# sem4200.net
KiCad netlist of a schematic drawn in Altium Designer
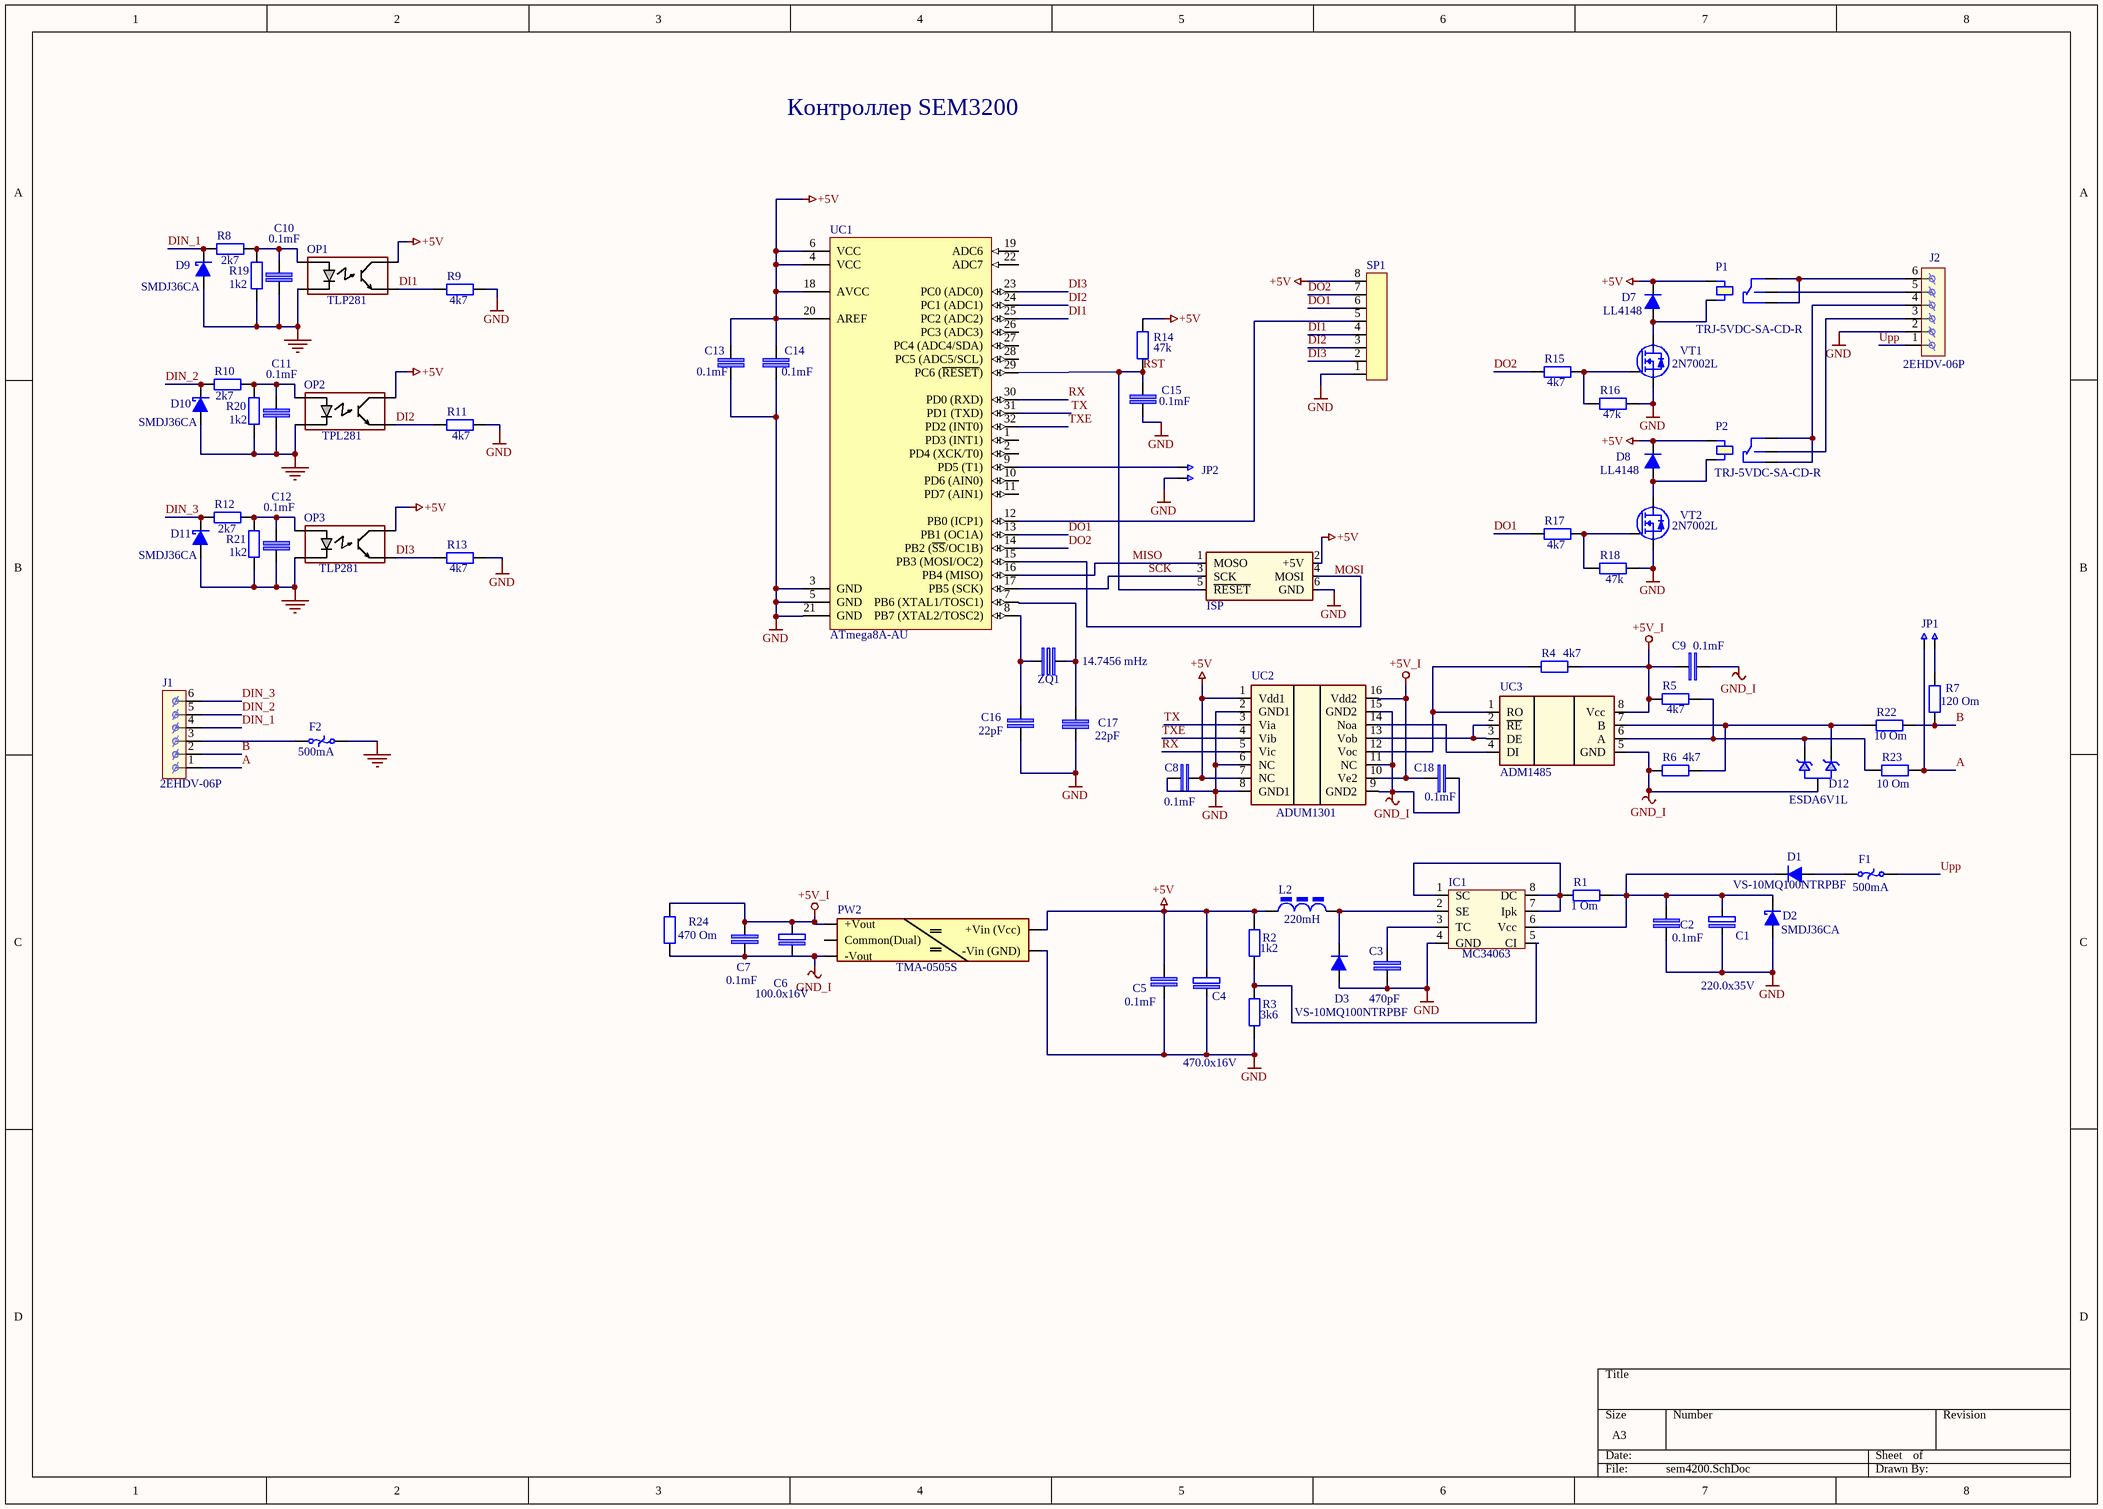
[diagram p0: sem4200.SchDoc]

(export (version "E")
  (design (tool "Eeschema 10.0.6"))
  (components
    (comp (ref "C1")
      (value "220.0x35V")
      (footprint "Cap_2(10x12.5)")
      (libsource (lib "Lib_my1") (part "Cap_pol2"))
    )
    (comp (ref "C2")
      (value "0.1mF")
      (footprint "CAPC2113X13N_0805")
      (fields (field (name "Comment") "0.1"))
      (libsource (lib "") (part "cap_1_1"))
    )
    (comp (ref "C3")
      (value "470pF")
      (footprint "CAPC2113X13N_0805")
      (fields (field (name "Comment") "470 pF"))
      (libsource (lib "") (part "cap_1_1"))
    )
    (comp (ref "C4")
      (value "470.0x16V")
      (footprint "Cap_2(10x12.5)")
      (fields (field (name "Comment") "470.0x35V"))
      (libsource (lib "Lib_my1") (part "Cap_pol2"))
    )
    (comp (ref "C5")
      (value "0.1mF")
      (footprint "CAPC2113X13N_0805")
      (fields (field (name "Comment") "0.1"))
      (libsource (lib "") (part "cap_1_1"))
    )
    (comp (ref "C6")
      (value "100.0x16V")
      (footprint "Cap_4(5x10)")
      (fields (field (name "Comment") "22.0x16V"))
      (libsource (lib "") (part "Cap_pol2_1"))
    )
    (comp (ref "C7")
      (value "0.1mF")
      (footprint "CAPC2113X13N_0805")
      (fields (field (name "Comment") "0.1"))
      (libsource (lib "Lib_my1") (part "cap_1"))
    )
    (comp (ref "C8")
      (value "0.1mF")
      (footprint "CAPC2113X13N_0805")
      (fields (field (name "Comment") "0.1"))
      (libsource (lib "Lib_my1") (part "cap_1"))
    )
    (comp (ref "C9")
      (value "0.1mF")
      (footprint "CAPC2113X13N_0805")
      (fields (field (name "Comment") "0.1"))
      (libsource (lib "Lib_my1") (part "cap_1"))
    )
    (comp (ref "C10")
      (value "0.1mF")
      (footprint "CAPC2113X13N_0805")
      (fields (field (name "Comment") "0.1"))
      (libsource (lib "Lib_my1") (part "cap_1"))
    )
    (comp (ref "C11")
      (value "0.1mF")
      (footprint "CAPC2113X13N_0805")
      (fields (field (name "Comment") "0.1"))
      (libsource (lib "Lib_my1") (part "cap_1"))
    )
    (comp (ref "C12")
      (value "0.1mF")
      (footprint "CAPC2113X13N_0805")
      (fields (field (name "Comment") "0.1"))
      (libsource (lib "Lib_my1") (part "cap_1"))
    )
    (comp (ref "C13")
      (value "0.1mF")
      (footprint "CAPC2113X13N_0805")
      (fields (field (name "Comment") "0.1"))
      (libsource (lib "Lib_my1") (part "cap_1"))
    )
    (comp (ref "C14")
      (value "0.1mF")
      (footprint "CAPC2113X13N_0805")
      (fields (field (name "Comment") "0.1"))
      (libsource (lib "Lib_my1") (part "cap_1"))
    )
    (comp (ref "C15")
      (value "0.1mF")
      (footprint "CAPC2113X13N_0805")
      (fields (field (name "Comment") "0.1"))
      (libsource (lib "") (part "cap_1_1"))
    )
    (comp (ref "C16")
      (value "22pF")
      (footprint "CAPC2113X13N_0805")
      (fields (field (name "Comment") "20p"))
      (libsource (lib "") (part "cap_1_1"))
    )
    (comp (ref "C17")
      (value "22pF")
      (footprint "CAPC2113X13N_0805")
      (fields (field (name "Comment") "20p"))
      (libsource (lib "") (part "cap_1_1"))
    )
    (comp (ref "C18")
      (value "0.1mF")
      (footprint "CAPC2113X13N_0805")
      (fields (field (name "Comment") "0.1"))
      (libsource (lib "") (part "cap_1_2"))
    )
    (comp (ref "D1")
      (value "SS18")
      (footprint "DIOD_SMA")
      (fields (field (name "TYPE") "VS-10MQ100NTRPBF"))
      (libsource (lib "Lib_my1") (part "Diod_30BQ100"))
    )
    (comp (ref "D2")
      (value "SMDJ36CA")
      (footprint "SMB_1")
      (fields (field (name "TYPE") "SMDJ36CA"))
      (libsource (lib "Lib_my1") (part "Diodes_SMB"))
    )
    (comp (ref "D3")
      (value "SS18")
      (footprint "DIOD_SMA")
      (fields (field (name "TYPE") "VS-10MQ100NTRPBF"))
      (libsource (lib "Lib_my1") (part "Diod_30BQ100"))
    )
    (comp (ref "D7")
      (value "LL4148")
      (footprint "DIOD_MELF_SOD80")
      (fields (field (name "TYPE") "LL4148"))
      (libsource (lib "Lib_my1") (part "Diodes_4148"))
    )
    (comp (ref "D8")
      (value "LL4148")
      (footprint "DIOD_MELF_SOD80")
      (fields (field (name "TYPE") "LL4148"))
      (libsource (lib "Lib_my1") (part "Diodes_4148"))
    )
    (comp (ref "D9")
      (value "SMDJ36CA")
      (footprint "SMB_1")
      (fields (field (name "TYPE") "SMDJ36CA"))
      (libsource (lib "Lib_my1") (part "Diodes_SMB"))
    )
    (comp (ref "D10")
      (value "SMDJ36CA")
      (footprint "SMB_1")
      (fields (field (name "TYPE") "SMDJ36CA"))
      (libsource (lib "Lib_my1") (part "Diodes_SMB"))
    )
    (comp (ref "D11")
      (value "SMDJ36CA")
      (footprint "SMB_1")
      (fields (field (name "TYPE") "SMDJ36CA"))
      (libsource (lib "Lib_my1") (part "Diodes_SMB"))
    )
    (comp (ref "D12")
      (value "ESDA6V1L")
      (footprint "SOT23_diod_ESDA")
      (fields (field (name "TYPE") "ESDA6V1L"))
      (libsource (lib "Lib_my1") (part "Diod_ESDA"))
    )
    (comp (ref "F1") (value "500mA") (footprint "Fuse_termo") (libsource (lib "Lib_my1") (part "Fuse_term")))
    (comp (ref "F2") (value "500mA") (footprint "Fuse_termo") (libsource (lib "Lib_my1") (part "Fuse_term")))
    (comp (ref "IC1")
      (value "MC34063")
      (footprint "SOIC_SO-8")
      (fields (field (name "TYPE") "MC34063"))
      (libsource (lib "Lib_my1") (part "MC34063_1"))
    )
    (comp (ref "ISP") (value "ISP") (footprint "ISP_1") (libsource (lib "Lib_my1") (part "ISP_1")))
    (comp (ref "J1")
      (value "Conn_6x1")
      (footprint "conn6X1")
      (fields (field (name "TYPE") "2EHDV-06P"))
      (libsource (lib "") (part "Conn_6x1_1"))
    )
    (comp (ref "J2")
      (value "Conn_6x1")
      (footprint "conn6X1")
      (fields (field (name "TYPE") "2EHDV-06P"))
      (libsource (lib "Lib_my1") (part "Conn_6x1"))
    )
    (comp (ref "JP1") (value "jamper") (footprint "JP_2_2.5") (libsource (lib "Lib_my1") (part "JP_2x2.5")))
    (comp (ref "JP2") (value "jamper") (footprint "JP_2_2.5") (libsource (lib "Lib_my1") (part "JP_2x2.5")))
    (comp (ref "L2") (value "220mH") (footprint "Dr_1") (libsource (lib "Lib_my1") (part "Dr_1")))
    (comp (ref "OP1")
      (value "TLP281GB")
      (footprint "SOIC127_TPL")
      (fields (field (name "TYPE") "TLP281"))
      (libsource (lib "Lib_my1") (part "opto_TLP"))
    )
    (comp (ref "OP2")
      (value "TLP281GB")
      (footprint "SOIC127_TPL")
      (fields (field (name "TYPE") "TPL281"))
      (libsource (lib "Lib_my1") (part "opto_TLP"))
    )
    (comp (ref "OP3")
      (value "TLP281GB")
      (footprint "SOIC127_TPL")
      (fields (field (name "TYPE") "TLP281"))
      (libsource (lib "Lib_my1") (part "opto_TLP"))
    )
    (comp (ref "P1")
      (value "TRJ")
      (footprint "PCB_rele_TRJ")
      (fields (field (name "TYPE") "TRJ-5VDC-SA-CD-R"))
      (libsource (lib "Lib_my1") (part "Rele_TRJ"))
    )
    (comp (ref "P2")
      (value "TRJ")
      (footprint "PCB_rele_TRJ")
      (fields (field (name "TYPE") "TRJ-5VDC-SA-CD-R"))
      (libsource (lib "Lib_my1") (part "Rele_TRJ"))
    )
    (comp (ref "PW2")
      (value "TMA_0505")
      (footprint "TMA_1W")
      (fields (field (name "TYPE") "TMA-0505S"))
      (libsource (lib "Lib_my1") (part "TRACO_PW1"))
    )
    (comp (ref "R1") (value "1 Om") (footprint "RES_1206") (libsource (lib "") (part "rez_1_1")))
    (comp (ref "R2") (value "1k2") (footprint "RESC2113X0805N") (libsource (lib "") (part "rez_1_2")))
    (comp (ref "R3") (value "3k6") (footprint "RESC2113X0805N") (libsource (lib "") (part "rez_1_2")))
    (comp (ref "R4")
      (value "4k7")
      (footprint "RESC2113X0805N")
      (fields (field (name "Comment") "10k"))
      (libsource (lib "Lib_my1") (part "rez_1"))
    )
    (comp (ref "R5") (value "4k7") (footprint "RESC2113X0805N") (libsource (lib "Lib_my1") (part "rez_1")))
    (comp (ref "R6") (value "4k7") (footprint "RESC2113X0805N") (libsource (lib "Lib_my1") (part "rez_1")))
    (comp (ref "R7") (value "120 Om") (footprint "RES_1206") (libsource (lib "") (part "rez_1_2")))
    (comp (ref "R8") (value "2k7") (footprint "Chip2Pin_2010") (libsource (lib "") (part "rez_1_1")))
    (comp (ref "R9") (value "4k7") (footprint "RESC2113X0805N") (libsource (lib "") (part "rez_1_1")))
    (comp (ref "R10") (value "2k7") (footprint "Chip2Pin_2010") (libsource (lib "") (part "rez_1_1")))
    (comp (ref "R11")
      (value "4k7")
      (footprint "RESC2113X0805N")
      (fields (field (name "Comment") "47k"))
      (libsource (lib "") (part "rez_1_1"))
    )
    (comp (ref "R12") (value "2k7") (footprint "Chip2Pin_2010") (libsource (lib "") (part "rez_1_1")))
    (comp (ref "R13")
      (value "4k7")
      (footprint "RESC2113X0805N")
      (fields (field (name "Comment") "47k"))
      (libsource (lib "") (part "rez_1_1"))
    )
    (comp (ref "R14") (value "47k") (footprint "RESC2113X0805N") (libsource (lib "") (part "rez_1_2")))
    (comp (ref "R15") (value "4k7") (footprint "RESC2113X0805N") (libsource (lib "Lib_my1") (part "rez_1")))
    (comp (ref "R16") (value "47k") (footprint "RESC2113X0805N") (libsource (lib "Lib_my1") (part "rez_1")))
    (comp (ref "R17") (value "4k7") (footprint "RESC2113X0805N") (libsource (lib "Lib_my1") (part "rez_1")))
    (comp (ref "R18") (value "47k") (footprint "RESC2113X0805N") (libsource (lib "Lib_my1") (part "rez_1")))
    (comp (ref "R19") (value "1k2") (footprint "RESC2113X0805N") (libsource (lib "") (part "rez_1_2")))
    (comp (ref "R20") (value "1k2") (footprint "RESC2113X0805N") (libsource (lib "") (part "rez_1_2")))
    (comp (ref "R21") (value "1k2") (footprint "RESC2113X0805N") (libsource (lib "") (part "rez_1_2")))
    (comp (ref "R22") (value "10 Om") (footprint "RESC2113X0805N") (libsource (lib "Lib_my1") (part "rez_1")))
    (comp (ref "R23") (value "10 Om") (footprint "RESC2113X0805N") (libsource (lib "Lib_my1") (part "rez_1")))
    (comp (ref "R24") (value "470 Om") (footprint "RES_1206") (libsource (lib "Lib_my1") (part "rez_1")))
    (comp (ref "SP1") (value "SP1") (footprint "Conn8x1") (libsource (lib "Lib_my1") (part "Conn8x1")))
    (comp (ref "UC1")
      (value "ATmega8A-AU")
      (footprint "32A_N")
      (fields (field (name "PUBLISHER") "Altium Limited"))
      (libsource (lib "Atmel Microcontroller 8-Bit megaAVR") (part "ATmega8A-AU"))
    )
    (comp (ref "UC2")
      (value "ADUM1301")
      (footprint "SOIC127P1030X265-16N_SOIC_W")
      (fields (field (name "TYPE") "ADUM1301"))
      (libsource (lib "Lib_my1") (part "ADUM1301"))
    )
    (comp (ref "UC3")
      (value "ADM1485")
      (footprint "SOIC127P600X175-8N_SOIC_SO8")
      (libsource (lib "Lib_my1") (part "ADM485"))
    )
    (comp (ref "VT1")
      (value "2N7002L")
      (footprint "SOT_23")
      (fields (field (name "TYPE") "2N7002L"))
      (libsource (lib "Lib_my1") (part "n_chanel_tranzistor1"))
    )
    (comp (ref "VT2")
      (value "2N7002L")
      (footprint "SOT_23")
      (fields (field (name "TYPE") "2N7002L"))
      (libsource (lib "Lib_my1") (part "n_chanel_tranzistor1"))
    )
    (comp (ref "ZQ1")
      (value "14.7456 mHz")
      (footprint "ZQ_1")
      (fields (field (name "Comment") "7.3728"))
      (libsource (lib "Lib_my1") (part "ZQ_1"))
    )
  )
  (nets
    (net (code "1") (name "+5V") (class "Default")
      (node (ref "C13") (pin "1") (pinfunction "1_1") (pintype "passive"))
      (node (ref "C14") (pin "1") (pinfunction "1_1") (pintype "passive"))
      (node (ref "C4") (pin "1") (pinfunction "1_1") (pintype "passive"))
      (node (ref "C5") (pin "1") (pinfunction "1_1") (pintype "passive"))
      (node (ref "C8") (pin "1") (pinfunction "1_1") (pintype "passive"))
      (node (ref "D7") (pin "2") (pinfunction "2_2") (pintype "passive"))
      (node (ref "D8") (pin "2") (pinfunction "2_2") (pintype "passive"))
      (node (ref "ISP") (pin "2") (pinfunction "+5V_2") (pintype "passive"))
      (node (ref "L2") (pin "2") (pinfunction "2_2") (pintype "passive"))
      (node (ref "OP1") (pin "4") (pinfunction "4_4") (pintype "passive"))
      (node (ref "OP2") (pin "4") (pinfunction "4_4") (pintype "passive"))
      (node (ref "OP3") (pin "4") (pinfunction "4_4") (pintype "passive"))
      (node (ref "P1") (pin "1") (pinfunction "1_1") (pintype "passive"))
      (node (ref "P2") (pin "1") (pinfunction "1_1") (pintype "passive"))
      (node (ref "PW2") (pin "1") (pinfunction "+Vin_(Vcc)_1") (pintype "passive"))
      (node (ref "R14") (pin "2") (pinfunction "2_2") (pintype "passive"))
      (node (ref "R2") (pin "2") (pinfunction "2_2") (pintype "passive"))
      (node (ref "SP1") (pin "8") (pinfunction "8_8") (pintype "passive"))
      (node (ref "UC1") (pin "18") (pinfunction "AVCC_18") (pintype "power_in"))
      (node (ref "UC1") (pin "20") (pinfunction "AREF_20") (pintype "power_in"))
      (node (ref "UC1") (pin "4") (pinfunction "VCC_4") (pintype "power_in"))
      (node (ref "UC1") (pin "6") (pinfunction "VCC_6") (pintype "power_in"))
      (node (ref "UC2") (pin "1") (pinfunction "Vdd1_1") (pintype "passive"))
      (node (ref "UC2") (pin "7") (pinfunction "NC_7") (pintype "passive"))
    )
    (net (code "2") (name "+5V_I") (class "Default")
      (node (ref "C18") (pin "1") (pinfunction "1_1") (pintype "passive"))
      (node (ref "C6") (pin "1") (pinfunction "1_1") (pintype "passive"))
      (node (ref "C7") (pin "1") (pinfunction "1_1") (pintype "passive"))
      (node (ref "C9") (pin "2") (pinfunction "2_2") (pintype "passive"))
      (node (ref "PW2") (pin "5") (pinfunction "+Vout_5") (pintype "passive"))
      (node (ref "R24") (pin "1") (pinfunction "1_1") (pintype "passive"))
      (node (ref "R4") (pin "1") (pinfunction "1_1") (pintype "passive"))
      (node (ref "R5") (pin "2") (pinfunction "2_2") (pintype "passive"))
      (node (ref "UC2") (pin "10") (pinfunction "Ve2_10") (pintype "passive"))
      (node (ref "UC2") (pin "16") (pinfunction "Vdd2_16") (pintype "passive"))
      (node (ref "UC3") (pin "8") (pinfunction "Vcc_8") (pintype "passive"))
    )
    (net (code "3") (name "/A") (class "Default")
      (node (ref "J1") (pin "1") (pinfunction "1_1") (pintype "passive"))
      (node (ref "JP1") (pin "1") (pinfunction "1_1") (pintype "passive"))
      (node (ref "R23") (pin "1") (pinfunction "1_1") (pintype "passive"))
    )
    (net (code "4") (name "/B") (class "Default")
      (node (ref "J1") (pin "2") (pinfunction "2_2") (pintype "passive"))
      (node (ref "R22") (pin "1") (pinfunction "1_1") (pintype "passive"))
      (node (ref "R7") (pin "1") (pinfunction "1_1") (pintype "passive"))
    )
    (net (code "5") (name "/DI1") (class "Default")
      (node (ref "OP1") (pin "3") (pinfunction "3_3") (pintype "passive"))
      (node (ref "R9") (pin "1") (pinfunction "1_1") (pintype "passive"))
      (node (ref "SP1") (pin "4") (pinfunction "4_4") (pintype "passive"))
      (node (ref "UC1") (pin "25") (pinfunction "PC2_(ADC2)_25") (pintype "bidirectional"))
    )
    (net (code "6") (name "/DI2") (class "Default")
      (node (ref "OP2") (pin "3") (pinfunction "3_3") (pintype "passive"))
      (node (ref "R11") (pin "1") (pinfunction "1_1") (pintype "passive"))
      (node (ref "SP1") (pin "3") (pinfunction "3_3") (pintype "passive"))
      (node (ref "UC1") (pin "24") (pinfunction "PC1_(ADC1)_24") (pintype "bidirectional"))
    )
    (net (code "7") (name "/DI3") (class "Default")
      (node (ref "OP3") (pin "3") (pinfunction "3_3") (pintype "passive"))
      (node (ref "R13") (pin "1") (pinfunction "1_1") (pintype "passive"))
      (node (ref "SP1") (pin "2") (pinfunction "2_2") (pintype "passive"))
      (node (ref "UC1") (pin "23") (pinfunction "PC0_(ADC0)_23") (pintype "bidirectional"))
    )
    (net (code "8") (name "/DIN_1") (class "Default")
      (node (ref "D9") (pin "1") (pinfunction "1_1") (pintype "passive"))
      (node (ref "J1") (pin "4") (pinfunction "4_4") (pintype "passive"))
      (node (ref "R8") (pin "1") (pinfunction "1_1") (pintype "passive"))
    )
    (net (code "9") (name "/DIN_2") (class "Default")
      (node (ref "D10") (pin "1") (pinfunction "1_1") (pintype "passive"))
      (node (ref "J1") (pin "5") (pinfunction "5_5") (pintype "passive"))
      (node (ref "R10") (pin "1") (pinfunction "1_1") (pintype "passive"))
    )
    (net (code "10") (name "/DIN_3") (class "Default")
      (node (ref "D11") (pin "1") (pinfunction "1_1") (pintype "passive"))
      (node (ref "J1") (pin "6") (pinfunction "6_6") (pintype "passive"))
      (node (ref "R12") (pin "1") (pinfunction "1_1") (pintype "passive"))
    )
    (net (code "11") (name "/DO1") (class "Default")
      (node (ref "R17") (pin "2") (pinfunction "2_2") (pintype "passive"))
      (node (ref "SP1") (pin "6") (pinfunction "6_6") (pintype "passive"))
      (node (ref "UC1") (pin "13") (pinfunction "PB1_(OC1A)_13") (pintype "bidirectional"))
    )
    (net (code "12") (name "/DO2") (class "Default")
      (node (ref "R15") (pin "2") (pinfunction "2_2") (pintype "passive"))
      (node (ref "SP1") (pin "7") (pinfunction "7_7") (pintype "passive"))
      (node (ref "UC1") (pin "14") (pinfunction "PB2_(~{SS}/OC1B)_14") (pintype "bidirectional"))
    )
    (net (code "13") (name "/MISO") (class "Default")
      (node (ref "ISP") (pin "1") (pinfunction "MOSO_1") (pintype "passive"))
      (node (ref "UC1") (pin "16") (pinfunction "PB4_(MISO)_16") (pintype "bidirectional"))
    )
    (net (code "15") (name "/RST") (class "Default")
      (node (ref "C15") (pin "1") (pinfunction "1_1") (pintype "passive"))
      (node (ref "ISP") (pin "5") (pinfunction "~{RESET}_5") (pintype "passive"))
      (node (ref "R14") (pin "1") (pinfunction "1_1") (pintype "passive"))
      (node (ref "UC1") (pin "29") (pinfunction "PC6_(~{RESET})_29") (pintype "bidirectional"))
    )
    (net (code "16") (name "/RX") (class "Default")
      (node (ref "UC1") (pin "30") (pinfunction "PD0_(RXD)_30") (pintype "bidirectional"))
      (node (ref "UC2") (pin "5") (pinfunction "Vic_5") (pintype "passive"))
    )
    (net (code "18") (name "/SCK") (class "Default")
      (node (ref "ISP") (pin "3") (pinfunction "SCK_3") (pintype "passive"))
      (node (ref "UC1") (pin "17") (pinfunction "PB5_(SCK)_17") (pintype "bidirectional"))
    )
    (net (code "19") (name "/TX") (class "Default")
      (node (ref "UC1") (pin "31") (pinfunction "PD1_(TXD)_31") (pintype "bidirectional"))
      (node (ref "UC2") (pin "3") (pinfunction "Via_3") (pintype "passive"))
    )
    (net (code "20") (name "/TXE") (class "Default")
      (node (ref "UC1") (pin "32") (pinfunction "PD2_(INT0)_32") (pintype "bidirectional"))
      (node (ref "UC2") (pin "4") (pinfunction "Vib_4") (pintype "passive"))
    )
    (net (code "21") (name "/Upp") (class "Default")
      (node (ref "F1") (pin "2") (pinfunction "2_2") (pintype "passive"))
      (node (ref "J2") (pin "1") (pinfunction "1_1") (pintype "passive"))
    )
    (net (code "22") (name "E_GND") (class "Default")
      (node (ref "C10") (pin "2") (pinfunction "2_2") (pintype "passive"))
      (node (ref "C11") (pin "2") (pinfunction "2_2") (pintype "passive"))
      (node (ref "C12") (pin "2") (pinfunction "2_2") (pintype "passive"))
      (node (ref "D10") (pin "2") (pinfunction "2_2") (pintype "passive"))
      (node (ref "D11") (pin "2") (pinfunction "2_2") (pintype "passive"))
      (node (ref "D9") (pin "2") (pinfunction "2_2") (pintype "passive"))
      (node (ref "F2") (pin "2") (pinfunction "2_2") (pintype "passive"))
      (node (ref "OP1") (pin "2") (pinfunction "2_2") (pintype "passive"))
      (node (ref "OP2") (pin "2") (pinfunction "2_2") (pintype "passive"))
      (node (ref "OP3") (pin "2") (pinfunction "2_2") (pintype "passive"))
      (node (ref "R19") (pin "1") (pinfunction "1_1") (pintype "passive"))
      (node (ref "R20") (pin "1") (pinfunction "1_1") (pintype "passive"))
      (node (ref "R21") (pin "1") (pinfunction "1_1") (pintype "passive"))
    )
    (net (code "23") (name "GND") (class "Default")
      (node (ref "C1") (pin "2") (pinfunction "2_2") (pintype "passive"))
      (node (ref "C13") (pin "2") (pinfunction "2_2") (pintype "passive"))
      (node (ref "C14") (pin "2") (pinfunction "2_2") (pintype "passive"))
      (node (ref "C15") (pin "2") (pinfunction "2_2") (pintype "passive"))
      (node (ref "C16") (pin "2") (pinfunction "2_2") (pintype "passive"))
      (node (ref "C17") (pin "2") (pinfunction "2_2") (pintype "passive"))
      (node (ref "C2") (pin "2") (pinfunction "2_2") (pintype "passive"))
      (node (ref "C3") (pin "2") (pinfunction "2_2") (pintype "passive"))
      (node (ref "C4") (pin "2") (pinfunction "2_2") (pintype "passive"))
      (node (ref "C5") (pin "2") (pinfunction "2_2") (pintype "passive"))
      (node (ref "C8") (pin "2") (pinfunction "2_2") (pintype "passive"))
      (node (ref "D2") (pin "2") (pinfunction "2_2") (pintype "passive"))
      (node (ref "D3") (pin "1") (pinfunction "1_1") (pintype "passive"))
      (node (ref "IC1") (pin "4") (pinfunction "GND_4") (pintype "passive"))
      (node (ref "ISP") (pin "6") (pinfunction "GND_6") (pintype "passive"))
      (node (ref "J2") (pin "2") (pinfunction "2_2") (pintype "passive"))
      (node (ref "JP2") (pin "2") (pinfunction "2_2") (pintype "passive"))
      (node (ref "PW2") (pin "2") (pinfunction "-Vin_(GND)_2") (pintype "passive"))
      (node (ref "R11") (pin "2") (pinfunction "2_2") (pintype "passive"))
      (node (ref "R13") (pin "2") (pinfunction "2_2") (pintype "passive"))
      (node (ref "R16") (pin "1") (pinfunction "1_1") (pintype "passive"))
      (node (ref "R18") (pin "1") (pinfunction "1_1") (pintype "passive"))
      (node (ref "R3") (pin "1") (pinfunction "1_1") (pintype "passive"))
      (node (ref "R9") (pin "2") (pinfunction "2_2") (pintype "passive"))
      (node (ref "SP1") (pin "1") (pinfunction "1_1") (pintype "passive"))
      (node (ref "UC1") (pin "21") (pinfunction "GND_21") (pintype "power_in"))
      (node (ref "UC1") (pin "3") (pinfunction "GND_3") (pintype "power_in"))
      (node (ref "UC1") (pin "5") (pinfunction "GND_5") (pintype "power_in"))
      (node (ref "UC2") (pin "2") (pinfunction "GND1_2") (pintype "passive"))
      (node (ref "UC2") (pin "6") (pinfunction "NC_6") (pintype "passive"))
      (node (ref "UC2") (pin "8") (pinfunction "GND1_8") (pintype "passive"))
      (node (ref "VT1") (pin "2") (pinfunction "2_2") (pintype "passive"))
      (node (ref "VT2") (pin "2") (pinfunction "2_2") (pintype "passive"))
    )
    (net (code "24") (name "GND_I") (class "Default")
      (node (ref "C18") (pin "2") (pinfunction "2_2") (pintype "passive"))
      (node (ref "C6") (pin "2") (pinfunction "2_2") (pintype "passive"))
      (node (ref "C7") (pin "2") (pinfunction "2_2") (pintype "passive"))
      (node (ref "C9") (pin "1") (pinfunction "1_1") (pintype "passive"))
      (node (ref "D12") (pin "3") (pinfunction "3_3") (pintype "passive"))
      (node (ref "PW2") (pin "3") (pinfunction "-Vout_3") (pintype "passive"))
      (node (ref "R24") (pin "2") (pinfunction "2_2") (pintype "passive"))
      (node (ref "R6") (pin "2") (pinfunction "2_2") (pintype "passive"))
      (node (ref "UC2") (pin "11") (pinfunction "NC_11") (pintype "passive"))
      (node (ref "UC2") (pin "15") (pinfunction "GND2_15") (pintype "passive"))
      (node (ref "UC2") (pin "9") (pinfunction "GND2_9") (pintype "passive"))
      (node (ref "UC3") (pin "5") (pinfunction "GND_5") (pintype "passive"))
    )
    (net (code "25") (name "Net-(C10-Pad1)") (class "Default")
      (node (ref "C10") (pin "1") (pinfunction "1_1") (pintype "passive"))
      (node (ref "OP1") (pin "1") (pinfunction "1_1") (pintype "passive"))
      (node (ref "R19") (pin "2") (pinfunction "2_2") (pintype "passive"))
      (node (ref "R8") (pin "2") (pinfunction "2_2") (pintype "passive"))
    )
    (net (code "26") (name "Net-(C11-Pad1)") (class "Default")
      (node (ref "C11") (pin "1") (pinfunction "1_1") (pintype "passive"))
      (node (ref "OP2") (pin "1") (pinfunction "1_1") (pintype "passive"))
      (node (ref "R10") (pin "2") (pinfunction "2_2") (pintype "passive"))
      (node (ref "R20") (pin "2") (pinfunction "2_2") (pintype "passive"))
    )
    (net (code "27") (name "Net-(C12-Pad1)") (class "Default")
      (node (ref "C12") (pin "1") (pinfunction "1_1") (pintype "passive"))
      (node (ref "OP3") (pin "1") (pinfunction "1_1") (pintype "passive"))
      (node (ref "R12") (pin "2") (pinfunction "2_2") (pintype "passive"))
      (node (ref "R21") (pin "2") (pinfunction "2_2") (pintype "passive"))
    )
    (net (code "28") (name "Net-(D1-Pad1)") (class "Default")
      (node (ref "D1") (pin "1") (pinfunction "1_1") (pintype "passive"))
      (node (ref "F1") (pin "1") (pinfunction "1_1") (pintype "passive"))
    )
    (net (code "29") (name "Net-(D7-Pad1)") (class "Default")
      (node (ref "D7") (pin "1") (pinfunction "1_1") (pintype "passive"))
      (node (ref "P1") (pin "5") (pinfunction "5_5") (pintype "passive"))
      (node (ref "VT1") (pin "3") (pinfunction "3_3") (pintype "passive"))
    )
    (net (code "30") (name "Net-(D8-Pad1)") (class "Default")
      (node (ref "D8") (pin "1") (pinfunction "1_1") (pintype "passive"))
      (node (ref "P2") (pin "5") (pinfunction "5_5") (pintype "passive"))
      (node (ref "VT2") (pin "3") (pinfunction "3_3") (pintype "passive"))
    )
    (net (code "31") (name "Net-(F2-Pad1)") (class "Default")
      (node (ref "F2") (pin "1") (pinfunction "1_1") (pintype "passive"))
      (node (ref "J1") (pin "3") (pinfunction "3_3") (pintype "passive"))
    )
    (net (code "32") (name "Net-(IC1-CI)") (class "Default")
      (node (ref "IC1") (pin "5") (pinfunction "CI_5") (pintype "passive"))
      (node (ref "R2") (pin "1") (pinfunction "1_1") (pintype "passive"))
      (node (ref "R3") (pin "2") (pinfunction "2_2") (pintype "passive"))
    )
    (net (code "33") (name "Net-(IC1-DC)") (class "Default")
      (node (ref "IC1") (pin "1") (pinfunction "SC_1") (pintype "passive"))
      (node (ref "IC1") (pin "7") (pinfunction "Ipk_7") (pintype "passive"))
      (node (ref "IC1") (pin "8") (pinfunction "DC_8") (pintype "passive"))
      (node (ref "R1") (pin "1") (pinfunction "1_1") (pintype "passive"))
    )
    (net (code "34") (name "Net-(IC1-SE)") (class "Default")
      (node (ref "D3") (pin "2") (pinfunction "2_2") (pintype "passive"))
      (node (ref "IC1") (pin "2") (pinfunction "SE_2") (pintype "passive"))
      (node (ref "L2") (pin "1") (pinfunction "1_1") (pintype "passive"))
    )
    (net (code "35") (name "Net-(IC1-TC)") (class "Default")
      (node (ref "C3") (pin "1") (pinfunction "1_1") (pintype "passive"))
      (node (ref "IC1") (pin "3") (pinfunction "TC_3") (pintype "passive"))
    )
    (net (code "36") (name "Net-(IC1-Vcc)") (class "Default")
      (node (ref "C1") (pin "1") (pinfunction "1_1") (pintype "passive"))
      (node (ref "C2") (pin "1") (pinfunction "1_1") (pintype "passive"))
      (node (ref "D1") (pin "2") (pinfunction "2_2") (pintype "passive"))
      (node (ref "D2") (pin "1") (pinfunction "1_1") (pintype "passive"))
      (node (ref "IC1") (pin "6") (pinfunction "Vcc_6") (pintype "passive"))
      (node (ref "R1") (pin "2") (pinfunction "2_2") (pintype "passive"))
    )
    (net (code "37") (name "Net-(ISP-MOSI)") (class "Default")
      (node (ref "ISP") (pin "4") (pinfunction "MOSI_4") (pintype "passive"))
      (node (ref "UC1") (pin "15") (pinfunction "PB3_(MOSI/OC2)_15") (pintype "bidirectional"))
    )
    (net (code "38") (name "Net-(J2-Pad3)") (class "Default")
      (node (ref "J2") (pin "3") (pinfunction "3_3") (pintype "passive"))
      (node (ref "P2") (pin "3") (pinfunction "3_3") (pintype "passive"))
    )
    (net (code "39") (name "Net-(J2-Pad4)") (class "Default")
      (node (ref "J2") (pin "4") (pinfunction "4_4") (pintype "passive"))
      (node (ref "P2") (pin "2") (pinfunction "2_2") (pintype "passive"))
      (node (ref "P2") (pin "4") (pinfunction "4_4") (pintype "passive"))
    )
    (net (code "40") (name "Net-(J2-Pad5)") (class "Default")
      (node (ref "J2") (pin "5") (pinfunction "5_5") (pintype "passive"))
      (node (ref "P1") (pin "3") (pinfunction "3_3") (pintype "passive"))
    )
    (net (code "41") (name "Net-(J2-Pad6)") (class "Default")
      (node (ref "J2") (pin "6") (pinfunction "6_6") (pintype "passive"))
      (node (ref "P1") (pin "2") (pinfunction "2_2") (pintype "passive"))
      (node (ref "P1") (pin "4") (pinfunction "4_4") (pintype "passive"))
    )
    (net (code "42") (name "Net-(JP1-Pad2)") (class "Default")
      (node (ref "JP1") (pin "2") (pinfunction "2_2") (pintype "passive"))
      (node (ref "R7") (pin "2") (pinfunction "2_2") (pintype "passive"))
    )
    (net (code "43") (name "Net-(R15-Pad1)") (class "Default")
      (node (ref "R15") (pin "1") (pinfunction "1_1") (pintype "passive"))
      (node (ref "R16") (pin "2") (pinfunction "2_2") (pintype "passive"))
      (node (ref "VT1") (pin "1") (pinfunction "1_1") (pintype "passive"))
    )
    (net (code "44") (name "Net-(R17-Pad1)") (class "Default")
      (node (ref "R17") (pin "1") (pinfunction "1_1") (pintype "passive"))
      (node (ref "R18") (pin "2") (pinfunction "2_2") (pintype "passive"))
      (node (ref "VT2") (pin "1") (pinfunction "1_1") (pintype "passive"))
    )
    (net (code "45") (name "Net-(UC1-PB0_(ICP1))") (class "Default")
      (node (ref "SP1") (pin "5") (pinfunction "5_5") (pintype "passive"))
      (node (ref "UC1") (pin "12") (pinfunction "PB0_(ICP1)_12") (pintype "bidirectional"))
    )
    (net (code "46") (name "Net-(UC1-PB6_(XTAL1{slash}TOSC1))") (class "Default")
      (node (ref "C17") (pin "1") (pinfunction "1_1") (pintype "passive"))
      (node (ref "UC1") (pin "7") (pinfunction "PB6_(XTAL1/TOSC1)_7") (pintype "bidirectional"))
      (node (ref "ZQ1") (pin "2") (pinfunction "2_2") (pintype "passive"))
    )
    (net (code "47") (name "Net-(UC1-PB7_(XTAL2{slash}TOSC2))") (class "Default")
      (node (ref "C16") (pin "1") (pinfunction "1_1") (pintype "passive"))
      (node (ref "UC1") (pin "8") (pinfunction "PB7_(XTAL2/TOSC2)_8") (pintype "bidirectional"))
      (node (ref "ZQ1") (pin "1") (pinfunction "1_1") (pintype "passive"))
    )
    (net (code "48") (name "Net-(UC1-PD5_(T1))") (class "Default")
      (node (ref "JP2") (pin "1") (pinfunction "1_1") (pintype "passive"))
      (node (ref "UC1") (pin "9") (pinfunction "PD5_(T1)_9") (pintype "bidirectional"))
    )
    (net (code "49") (name "Net-(UC2-Noa)") (class "Default")
      (node (ref "UC2") (pin "14") (pinfunction "Noa_14") (pintype "passive"))
      (node (ref "UC3") (pin "4") (pinfunction "DI_4") (pintype "passive"))
    )
    (net (code "50") (name "Net-(UC2-Vob)") (class "Default")
      (node (ref "UC2") (pin "13") (pinfunction "Vob_13") (pintype "passive"))
      (node (ref "UC3") (pin "2") (pinfunction "~{RE}_2") (pintype "passive"))
      (node (ref "UC3") (pin "3") (pinfunction "DE_3") (pintype "passive"))
    )
    (net (code "51") (name "Net-(UC2-Voc)") (class "Default")
      (node (ref "R4") (pin "2") (pinfunction "2_2") (pintype "passive"))
      (node (ref "UC2") (pin "12") (pinfunction "Voc_12") (pintype "passive"))
      (node (ref "UC3") (pin "1") (pinfunction "RO_1") (pintype "passive"))
    )
    (net (code "52") (name "Net-(UC3-A)") (class "Default")
      (node (ref "D12") (pin "2") (pinfunction "2_2") (pintype "passive"))
      (node (ref "R23") (pin "2") (pinfunction "2_2") (pintype "passive"))
      (node (ref "R5") (pin "1") (pinfunction "1_1") (pintype "passive"))
      (node (ref "UC3") (pin "6") (pinfunction "A_6") (pintype "passive"))
    )
    (net (code "53") (name "Net-(UC3-B)") (class "Default")
      (node (ref "D12") (pin "1") (pinfunction "1_1") (pintype "passive"))
      (node (ref "R22") (pin "2") (pinfunction "2_2") (pintype "passive"))
      (node (ref "R6") (pin "1") (pinfunction "1_1") (pintype "passive"))
      (node (ref "UC3") (pin "7") (pinfunction "B_7") (pintype "passive"))
    )
    (net (code "54") (name "unconnected-(PW2-Common(Dual)-Pad4)") (class "Default")
      (node (ref "PW2") (pin "4") (pinfunction "Common(Dual)_4") (pintype "passive"))
    )
    (net (code "55") (name "unconnected-(UC1-ADC6-Pad19)") (class "Default")
      (node (ref "UC1") (pin "19") (pinfunction "ADC6_19") (pintype "input"))
    )
    (net (code "56") (name "unconnected-(UC1-ADC7-Pad22)") (class "Default")
      (node (ref "UC1") (pin "22") (pinfunction "ADC7_22") (pintype "input"))
    )
    (net (code "57") (name "unconnected-(UC1-PC3_(ADC3)-Pad26)") (class "Default")
      (node (ref "UC1") (pin "26") (pinfunction "PC3_(ADC3)_26") (pintype "bidirectional"))
    )
    (net (code "58") (name "unconnected-(UC1-PC4_(ADC4{slash}SDA)-Pad27)") (class "Default")
      (node (ref "UC1") (pin "27") (pinfunction "PC4_(ADC4/SDA)_27") (pintype "bidirectional"))
    )
    (net (code "59") (name "unconnected-(UC1-PC5_(ADC5{slash}SCL)-Pad28)") (class "Default")
      (node (ref "UC1") (pin "28") (pinfunction "PC5_(ADC5/SCL)_28") (pintype "bidirectional"))
    )
    (net (code "60") (name "unconnected-(UC1-PD3_(INT1)-Pad1)") (class "Default")
      (node (ref "UC1") (pin "1") (pinfunction "PD3_(INT1)_1") (pintype "bidirectional"))
    )
    (net (code "61") (name "unconnected-(UC1-PD4_(XCK{slash}T0)-Pad2)") (class "Default")
      (node (ref "UC1") (pin "2") (pinfunction "PD4_(XCK/T0)_2") (pintype "bidirectional"))
    )
    (net (code "62") (name "unconnected-(UC1-PD6_(AIN0)-Pad10)") (class "Default")
      (node (ref "UC1") (pin "10") (pinfunction "PD6_(AIN0)_10") (pintype "bidirectional"))
    )
    (net (code "63") (name "unconnected-(UC1-PD7_(AIN1)-Pad11)") (class "Default")
      (node (ref "UC1") (pin "11") (pinfunction "PD7_(AIN1)_11") (pintype "bidirectional"))
    )
  )
)
